# Sch_external_connectors.net
KiCad netlist of a schematic drawn in Altium Designer
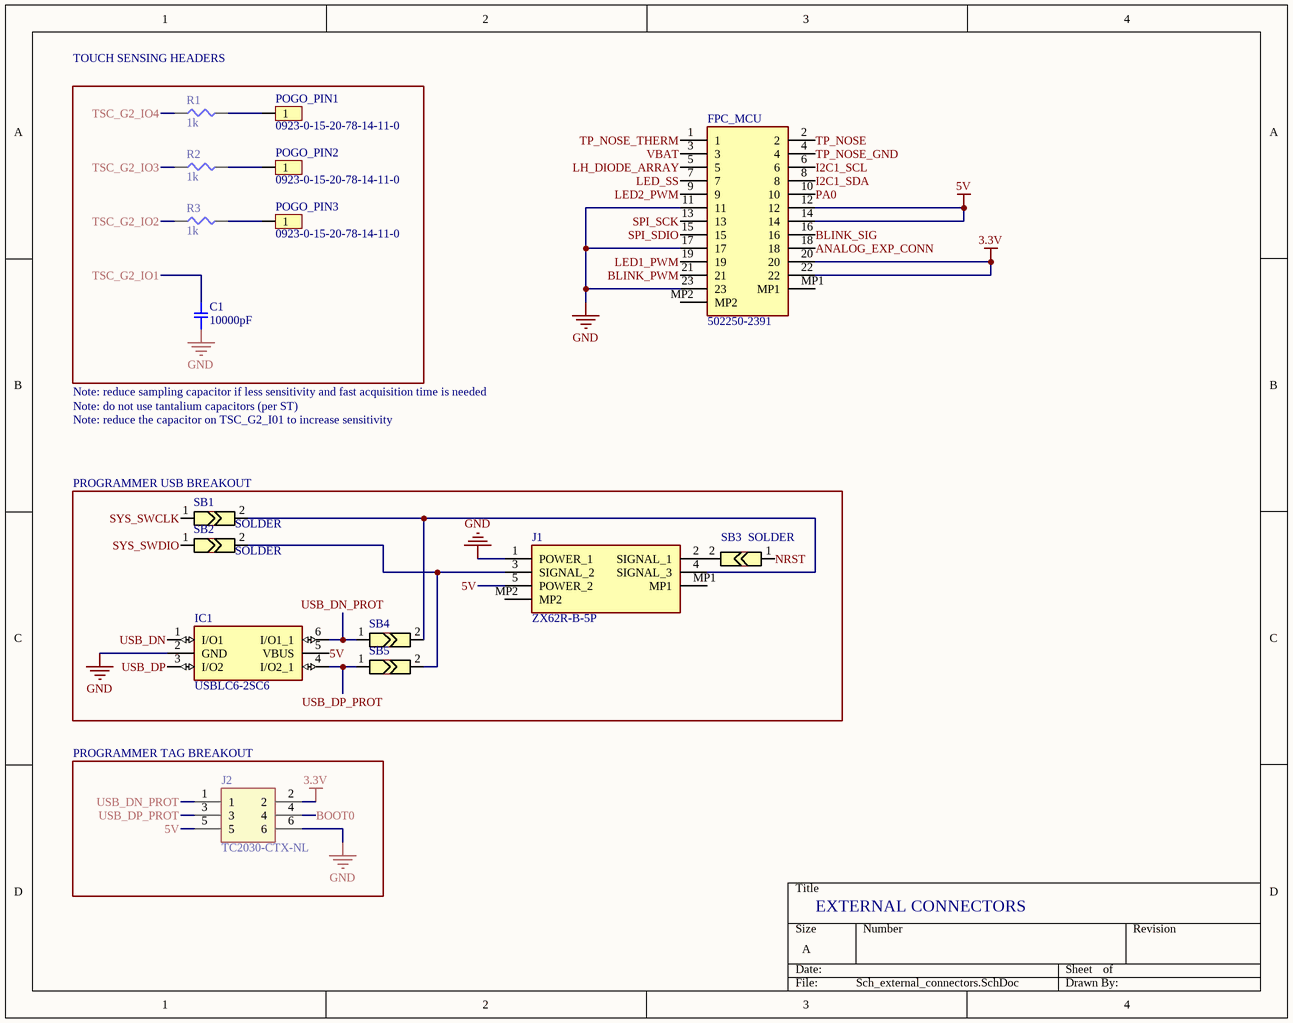
[diagram p0: Sch_external_connectors.SchDoc]

(export (version "E")
  (design (tool "Eeschema 10.0.6"))
  (components
    (comp (ref "C1")
      (value "10000pF")
      (footprint "SMD-0402C")
      (description "CAP CER 10000PF 50V X7R 0402")
      (fields
        (field (name "DIGI-KEY PART NUMBER") "490-4762-1-ND")
        (field (name "PART NUMBER") "GCM155R71H103KA55D")
      )
      (libsource (lib "capacitor_murata_0402") (part "GCM155R71H103KA55D"))
    )
    (comp (ref "FPC_MCU")
      (value "502250-2391")
      (footprint "SamacSys:5022502391")
      (description "Connector")
      (fields (field (name "MOUSER PART NUMBER") "538-502250-2391"))
      (libsource (lib "*") (part "502250-2391"))
    )
    (comp (ref "IC1")
      (value "USBLC6-2SC6")
      (footprint "SamacSys:SOT95P280X145-6N")
      (description "Integrated Circuit")
      (fields (field (name "MOUSER PART NUMBER") "511-USBLC6-2SC6") (field (name "RS PART NUMBER") "9206266"))
      (libsource (lib "*") (part "USBLC6-2SC6"))
    )
    (comp (ref "J1")
      (value "ZX62R-B-5P")
      (footprint "SamacSys:USB307030A")
      (description "Connector")
      (fields (field (name "MANUFACTURER_PART_NUMBER") "USB3070-30-A"))
      (libsource (lib "*") (part "USB3070-30-A"))
    )
    (comp (ref "J2")
      (value "TC2030-CTX-NL")
      (footprint "SamacSys:TC2030MCPNL10")
      (description "Connector")
      (libsource (lib "*") (part "TC2030-CTX-NL"))
    )
    (comp (ref "POGO_PIN1")
      (value "0923-0-15-20-78-14-11-0")
      (footprint "0923-0-15-20-78-14-11-0")
      (libsource (lib "schematic_components") (part "0923-0-15-20-78-14-11-0"))
    )
    (comp (ref "POGO_PIN2")
      (value "0923-0-15-20-78-14-11-0")
      (footprint "0923-0-15-20-78-14-11-0")
      (libsource (lib "schematic_components") (part "0923-0-15-20-78-14-11-0"))
    )
    (comp (ref "POGO_PIN3")
      (value "0923-0-15-20-78-14-11-0")
      (footprint "0923-0-15-20-78-14-11-0")
      (libsource (lib "schematic_components") (part "0923-0-15-20-78-14-11-0"))
    )
    (comp (ref "R1")
      (value "1k")
      (footprint "SMD-0402-RES")
      (description "RES SMD 1K OHM 5% 1/10W 0402")
      (fields (field (name "PART NUMBER") "ERJ-2GEJ102X") (field (name "DIGI-KEY PART NUMBER") "P1.0KJCT-ND"))
      (libsource (lib "Panasonic_ERJ_0402") (part "ERJ-2GEJ102X"))
    )
    (comp (ref "R2")
      (value "1k")
      (footprint "SMD-0402-RES")
      (description "RES SMD 1K OHM 5% 1/10W 0402")
      (fields (field (name "PART NUMBER") "ERJ-2GEJ102X") (field (name "DIGI-KEY PART NUMBER") "P1.0KJCT-ND"))
      (libsource (lib "Panasonic_ERJ_0402") (part "ERJ-2GEJ102X"))
    )
    (comp (ref "R3")
      (value "1k")
      (footprint "SMD-0402-RES")
      (description "RES SMD 1K OHM 5% 1/10W 0402")
      (fields (field (name "PART NUMBER") "ERJ-2GEJ102X") (field (name "DIGI-KEY PART NUMBER") "P1.0KJCT-ND"))
      (libsource (lib "Panasonic_ERJ_0402") (part "ERJ-2GEJ102X"))
    )
    (comp (ref "SB1")
      (value "SOLDER_JUMPER")
      (footprint "custom_footprints:JUMPER_SMD")
      (libsource (lib "SamacSys") (part "SOLDER_JUMPER"))
    )
    (comp (ref "SB2")
      (value "SOLDER_JUMPER")
      (footprint "custom_footprints:JUMPER_SMD")
      (libsource (lib "SamacSys") (part "SOLDER_JUMPER"))
    )
    (comp (ref "SB3")
      (value "SOLDER_JUMPER")
      (footprint "custom_footprints:JUMPER_SMD")
      (libsource (lib "") (part "SOLDER_JUMPER_1"))
    )
    (comp (ref "SB4")
      (value "SOLDER_JUMPER")
      (footprint "custom_footprints:JUMPER_SMD")
      (libsource (lib "custom_general") (part "SOLDER_JUMPER"))
    )
    (comp (ref "SB5")
      (value "SOLDER_JUMPER")
      (footprint "custom_footprints:JUMPER_SMD")
      (libsource (lib "SamacSys") (part "SOLDER_JUMPER"))
    )
  )
  (nets
    (net (code "1") (name "/ANALOG_EXP_CONN") (class "Default")
      (node (ref "FPC_MCU") (pin "18") (pinfunction "18_18") (pintype "passive"))
    )
    (net (code "2") (name "/BLINK_PWM") (class "Default")
      (node (ref "FPC_MCU") (pin "21") (pinfunction "21_21") (pintype "passive"))
    )
    (net (code "3") (name "/BLINK_SIG") (class "Default")
      (node (ref "FPC_MCU") (pin "16") (pinfunction "16_16") (pintype "passive"))
    )
    (net (code "4") (name "/BOOT0") (class "Default")
      (node (ref "J2") (pin "4") (pinfunction "4_4") (pintype "passive"))
    )
    (net (code "5") (name "/I2C1_SCL") (class "Default")
      (node (ref "FPC_MCU") (pin "6") (pinfunction "6_6") (pintype "passive"))
    )
    (net (code "6") (name "/I2C1_SDA") (class "Default")
      (node (ref "FPC_MCU") (pin "8") (pinfunction "8_8") (pintype "passive"))
    )
    (net (code "7") (name "/LED1_PWM") (class "Default")
      (node (ref "FPC_MCU") (pin "19") (pinfunction "19_19") (pintype "passive"))
    )
    (net (code "8") (name "/LED2_PWM") (class "Default")
      (node (ref "FPC_MCU") (pin "9") (pinfunction "9_9") (pintype "passive"))
    )
    (net (code "9") (name "/LED_SS") (class "Default")
      (node (ref "FPC_MCU") (pin "7") (pinfunction "7_7") (pintype "passive"))
    )
    (net (code "10") (name "/LH_DIODE_ARRAY") (class "Default")
      (node (ref "FPC_MCU") (pin "5") (pinfunction "5_5") (pintype "passive"))
    )
    (net (code "11") (name "/NRST") (class "Default")
      (node (ref "SB3") (pin "1") (pinfunction "1_1") (pintype "passive"))
    )
    (net (code "12") (name "/PA0") (class "Default")
      (node (ref "FPC_MCU") (pin "10") (pinfunction "10_10") (pintype "passive"))
    )
    (net (code "13") (name "/SPI_SCK") (class "Default")
      (node (ref "FPC_MCU") (pin "13") (pinfunction "13_13") (pintype "passive"))
    )
    (net (code "14") (name "/SPI_SDIO") (class "Default")
      (node (ref "FPC_MCU") (pin "15") (pinfunction "15_15") (pintype "passive"))
    )
    (net (code "15") (name "/SYS_SWCLK") (class "Default")
      (node (ref "SB1") (pin "1") (pinfunction "1_1") (pintype "passive"))
    )
    (net (code "16") (name "/SYS_SWDIO") (class "Default")
      (node (ref "SB2") (pin "1") (pinfunction "1_1") (pintype "passive"))
    )
    (net (code "17") (name "/TP_NOSE") (class "Default")
      (node (ref "FPC_MCU") (pin "2") (pinfunction "2_2") (pintype "passive"))
    )
    (net (code "18") (name "/TP_NOSE_GND") (class "Default")
      (node (ref "FPC_MCU") (pin "4") (pinfunction "4_4") (pintype "passive"))
    )
    (net (code "19") (name "/TP_NOSE_THERM") (class "Default")
      (node (ref "FPC_MCU") (pin "1") (pinfunction "1_1") (pintype "passive"))
    )
    (net (code "20") (name "/TSC_G2_IO1") (class "Default")
      (node (ref "C1") (pin "2") (pinfunction "2_2") (pintype "passive"))
    )
    (net (code "21") (name "/TSC_G2_IO2") (class "Default")
      (node (ref "R3") (pin "1") (pinfunction "1_1") (pintype "passive"))
    )
    (net (code "22") (name "/TSC_G2_IO3") (class "Default")
      (node (ref "R2") (pin "1") (pinfunction "1_1") (pintype "passive"))
    )
    (net (code "23") (name "/TSC_G2_IO4") (class "Default")
      (node (ref "R1") (pin "1") (pinfunction "1_1") (pintype "passive"))
    )
    (net (code "24") (name "/USB_DN") (class "Default")
      (node (ref "IC1") (pin "1") (pinfunction "I/O1_1") (pintype "bidirectional"))
    )
    (net (code "25") (name "/USB_DN_PROT") (class "Default")
      (node (ref "IC1") (pin "6") (pinfunction "I/O1_1_6") (pintype "bidirectional"))
      (node (ref "J2") (pin "1") (pinfunction "1_1") (pintype "passive"))
      (node (ref "SB4") (pin "1") (pinfunction "1_1") (pintype "passive"))
    )
    (net (code "26") (name "/USB_DP") (class "Default")
      (node (ref "IC1") (pin "3") (pinfunction "I/O2_3") (pintype "bidirectional"))
    )
    (net (code "27") (name "/USB_DP_PROT") (class "Default")
      (node (ref "IC1") (pin "4") (pinfunction "I/O2_1_4") (pintype "bidirectional"))
      (node (ref "J2") (pin "3") (pinfunction "3_3") (pintype "passive"))
      (node (ref "SB5") (pin "1") (pinfunction "1_1") (pintype "passive"))
    )
    (net (code "28") (name "/VBAT") (class "Default")
      (node (ref "FPC_MCU") (pin "3") (pinfunction "3_3") (pintype "passive"))
    )
    (net (code "29") (name "3.3V") (class "Default")
      (node (ref "FPC_MCU") (pin "20") (pinfunction "20_20") (pintype "passive"))
      (node (ref "FPC_MCU") (pin "22") (pinfunction "22_22") (pintype "passive"))
      (node (ref "J2") (pin "2") (pinfunction "2_2") (pintype "passive"))
    )
    (net (code "30") (name "5V") (class "Default")
      (node (ref "FPC_MCU") (pin "12") (pinfunction "12_12") (pintype "passive"))
      (node (ref "FPC_MCU") (pin "14") (pinfunction "14_14") (pintype "passive"))
      (node (ref "IC1") (pin "5") (pinfunction "VBUS_5") (pintype "passive"))
      (node (ref "J1") (pin "5") (pinfunction "POWER_2_5") (pintype "passive"))
      (node (ref "J2") (pin "5") (pinfunction "5_5") (pintype "passive"))
    )
    (net (code "31") (name "GND") (class "Default")
      (node (ref "C1") (pin "1") (pinfunction "1_1") (pintype "passive"))
      (node (ref "FPC_MCU") (pin "11") (pinfunction "11_11") (pintype "passive"))
      (node (ref "FPC_MCU") (pin "17") (pinfunction "17_17") (pintype "passive"))
      (node (ref "FPC_MCU") (pin "23") (pinfunction "23_23") (pintype "passive"))
      (node (ref "IC1") (pin "2") (pinfunction "GND_2") (pintype "power_in"))
      (node (ref "J1") (pin "1") (pinfunction "POWER_1_1") (pintype "passive"))
      (node (ref "J2") (pin "6") (pinfunction "6_6") (pintype "passive"))
    )
    (net (code "32") (name "Net-(J1-SIGNAL_1)") (class "Default")
      (node (ref "J1") (pin "2") (pinfunction "SIGNAL_1_2") (pintype "passive"))
      (node (ref "SB3") (pin "2") (pinfunction "1_2") (pintype "passive"))
    )
    (net (code "33") (name "Net-(J1-SIGNAL_2)") (class "Default")
      (node (ref "J1") (pin "3") (pinfunction "SIGNAL_2_3") (pintype "passive"))
      (node (ref "SB2") (pin "2") (pinfunction "1_2") (pintype "passive"))
      (node (ref "SB5") (pin "2") (pinfunction "1_2") (pintype "passive"))
    )
    (net (code "34") (name "Net-(J1-SIGNAL_3)") (class "Default")
      (node (ref "J1") (pin "4") (pinfunction "SIGNAL_3_4") (pintype "passive"))
      (node (ref "SB1") (pin "2") (pinfunction "1_2") (pintype "passive"))
      (node (ref "SB4") (pin "2") (pinfunction "1_2") (pintype "passive"))
    )
    (net (code "35") (name "Net-(POGO_PIN1-Pad1)") (class "Default")
      (node (ref "POGO_PIN1") (pin "1") (pinfunction "1_1") (pintype "passive"))
      (node (ref "R1") (pin "2") (pinfunction "2_2") (pintype "passive"))
    )
    (net (code "36") (name "Net-(POGO_PIN2-Pad1)") (class "Default")
      (node (ref "POGO_PIN2") (pin "1") (pinfunction "1_1") (pintype "passive"))
      (node (ref "R2") (pin "2") (pinfunction "2_2") (pintype "passive"))
    )
    (net (code "37") (name "Net-(POGO_PIN3-Pad1)") (class "Default")
      (node (ref "POGO_PIN3") (pin "1") (pinfunction "1_1") (pintype "passive"))
      (node (ref "R3") (pin "2") (pinfunction "2_2") (pintype "passive"))
    )
    (net (code "38") (name "unconnected-(FPC_MCU-PadMP1)") (class "Default")
      (node (ref "FPC_MCU") (pin "MP1") (pinfunction "MP1_MP1") (pintype "passive"))
    )
    (net (code "39") (name "unconnected-(FPC_MCU-PadMP2)") (class "Default")
      (node (ref "FPC_MCU") (pin "MP2") (pinfunction "MP2_MP2") (pintype "passive"))
    )
    (net (code "40") (name "unconnected-(J1-PadMP1)") (class "Default")
      (node (ref "J1") (pin "MP1") (pinfunction "MP1_MP1") (pintype "passive"))
    )
    (net (code "41") (name "unconnected-(J1-PadMP2)") (class "Default")
      (node (ref "J1") (pin "MP2") (pinfunction "MP2_MP2") (pintype "passive"))
    )
  )
)
